# LED_SCH.net
KiCad netlist of a schematic drawn in Altium Designer
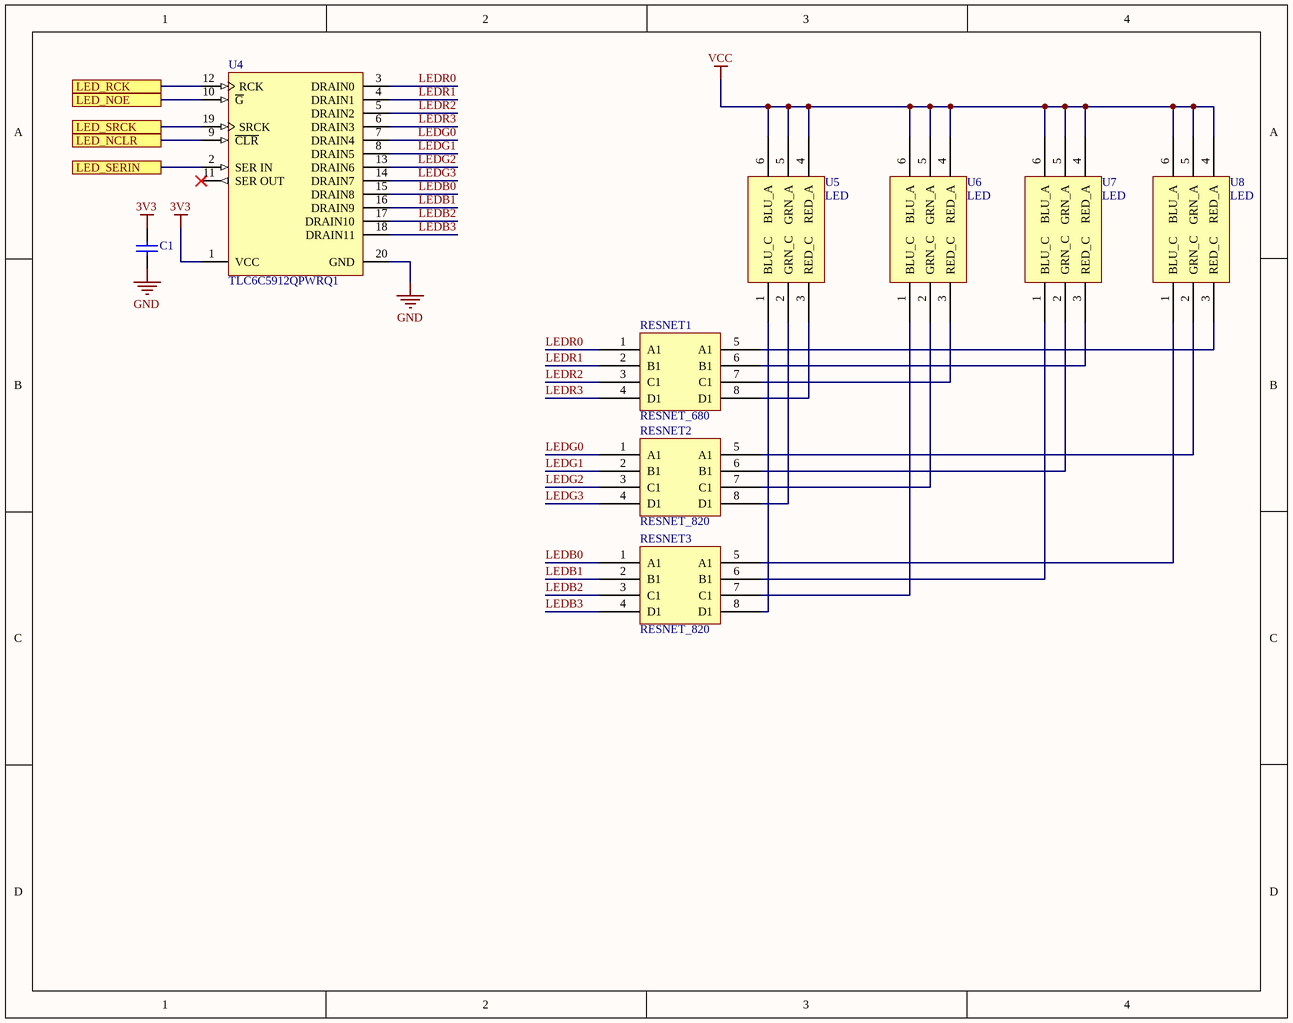
[diagram p0: LED_SCH.SchDoc]

(export (version "E")
  (design (tool "Eeschema 10.0.6"))
  (components
    (comp (ref "C1")
      (value "08055C104KAJ2A")
      (footprint "CAPC2013X140X50NL20T25")
      (fields (field (name "MANUFACTURER") "AVX Interconnect / Elco"))
      (libsource (lib "Altium Content Vault") (part "CAP"))
    )
    (comp (ref "RESNET1")
      (value "RESNET_680")
      (footprint "CAC-80P320X165-8N")
      (description "RES ARRAY 4 RES 680 OHM 2012")
      (libsource (lib "Copter") (part "RESNET_680"))
    )
    (comp (ref "RESNET2")
      (value "RESNET_820")
      (footprint "74X_RESNET")
      (description "RES ARRAY 4 RES 820 OHM 2012")
      (libsource (lib "Copter") (part "RESNET_820"))
    )
    (comp (ref "RESNET3")
      (value "RESNET_820")
      (footprint "74X_RESNET")
      (description "RES ARRAY 4 RES 820 OHM 2012")
      (libsource (lib "Copter") (part "RESNET_820"))
    )
    (comp (ref "U4")
      (value "TLC6C5912QPWRQ1")
      (footprint "PW0020A_N")
      (description "Automotive Power Logic 12-Bit Shift Register LED Driver, PW0020A, LARGE T&R")
      (fields (field (name "PART NUMBER") "TLC6C5912-Q1"))
      (libsource (lib "Altium Content Vault") (part "TI-TLC6C5912-Q1-20_A"))
    )
    (comp (ref "U5") (value "LED") (footprint "PLCC6") (libsource (lib "Copter") (part "LED")))
    (comp (ref "U6") (value "LED") (footprint "PLCC6") (libsource (lib "Copter") (part "LED")))
    (comp (ref "U7") (value "LED") (footprint "PLCC6") (libsource (lib "Copter") (part "LED")))
    (comp (ref "U8") (value "LED") (footprint "PLCC6") (libsource (lib "Copter") (part "LED")))
  )
  (nets
    (net (code "1") (name "/LEDB0") (class "Default")
      (node (ref "RESNET3") (pin "1") (pinfunction "A1_1") (pintype "passive"))
      (node (ref "U4") (pin "15") (pinfunction "DRAIN8_15") (pintype "open_collector"))
    )
    (net (code "2") (name "/LEDB1") (class "Default")
      (node (ref "RESNET3") (pin "2") (pinfunction "B1_2") (pintype "passive"))
      (node (ref "U4") (pin "16") (pinfunction "DRAIN9_16") (pintype "open_collector"))
    )
    (net (code "3") (name "/LEDB2") (class "Default")
      (node (ref "RESNET3") (pin "3") (pinfunction "C1_3") (pintype "passive"))
      (node (ref "U4") (pin "17") (pinfunction "DRAIN10_17") (pintype "open_collector"))
    )
    (net (code "4") (name "/LEDB3") (class "Default")
      (node (ref "RESNET3") (pin "4") (pinfunction "D1_4") (pintype "passive"))
      (node (ref "U4") (pin "18") (pinfunction "DRAIN11_18") (pintype "open_collector"))
    )
    (net (code "5") (name "/LEDG0") (class "Default")
      (node (ref "RESNET2") (pin "1") (pinfunction "A1_1") (pintype "passive"))
      (node (ref "U4") (pin "7") (pinfunction "DRAIN4_7") (pintype "open_collector"))
    )
    (net (code "6") (name "/LEDG1") (class "Default")
      (node (ref "RESNET2") (pin "2") (pinfunction "B1_2") (pintype "passive"))
      (node (ref "U4") (pin "8") (pinfunction "DRAIN5_8") (pintype "open_collector"))
    )
    (net (code "7") (name "/LEDG2") (class "Default")
      (node (ref "RESNET2") (pin "3") (pinfunction "C1_3") (pintype "passive"))
      (node (ref "U4") (pin "13") (pinfunction "DRAIN6_13") (pintype "open_collector"))
    )
    (net (code "8") (name "/LEDG3") (class "Default")
      (node (ref "RESNET2") (pin "4") (pinfunction "D1_4") (pintype "passive"))
      (node (ref "U4") (pin "14") (pinfunction "DRAIN7_14") (pintype "open_collector"))
    )
    (net (code "9") (name "/LEDR0") (class "Default")
      (node (ref "RESNET1") (pin "1") (pinfunction "A1_1") (pintype "passive"))
      (node (ref "U4") (pin "3") (pinfunction "DRAIN0_3") (pintype "open_collector"))
    )
    (net (code "10") (name "/LEDR1") (class "Default")
      (node (ref "RESNET1") (pin "2") (pinfunction "B1_2") (pintype "passive"))
      (node (ref "U4") (pin "4") (pinfunction "DRAIN1_4") (pintype "open_collector"))
    )
    (net (code "11") (name "/LEDR2") (class "Default")
      (node (ref "RESNET1") (pin "3") (pinfunction "C1_3") (pintype "passive"))
      (node (ref "U4") (pin "5") (pinfunction "DRAIN2_5") (pintype "open_collector"))
    )
    (net (code "12") (name "/LEDR3") (class "Default")
      (node (ref "RESNET1") (pin "4") (pinfunction "D1_4") (pintype "passive"))
      (node (ref "U4") (pin "6") (pinfunction "DRAIN3_6") (pintype "open_collector"))
    )
    (net (code "13") (name "/LED_NCLR") (class "Default")
      (node (ref "U4") (pin "9") (pinfunction "~{CLR}_9") (pintype "input"))
    )
    (net (code "14") (name "/LED_NOE") (class "Default")
      (node (ref "U4") (pin "10") (pinfunction "~{G}_10") (pintype "input"))
    )
    (net (code "15") (name "/LED_RCK") (class "Default")
      (node (ref "U4") (pin "12") (pinfunction "RCK_12") (pintype "input"))
    )
    (net (code "16") (name "/LED_SERIN") (class "Default")
      (node (ref "U4") (pin "2") (pinfunction "SER_IN_2") (pintype "input"))
    )
    (net (code "17") (name "/LED_SRCK") (class "Default")
      (node (ref "U4") (pin "19") (pinfunction "SRCK_19") (pintype "input"))
    )
    (net (code "18") (name "3V3") (class "Default")
      (node (ref "C1") (pin "2") (pinfunction "2_2") (pintype "passive"))
      (node (ref "U4") (pin "1") (pinfunction "VCC_1") (pintype "power_in"))
    )
    (net (code "19") (name "GND") (class "Default")
      (node (ref "C1") (pin "1") (pinfunction "1_1") (pintype "passive"))
      (node (ref "U4") (pin "20") (pinfunction "GND_20") (pintype "power_in"))
    )
    (net (code "20") (name "Net-(U5-BLU_C)") (class "Default")
      (node (ref "RESNET3") (pin "8") (pinfunction "D1_8") (pintype "passive"))
      (node (ref "U5") (pin "1") (pinfunction "BLU_C_1") (pintype "passive"))
    )
    (net (code "21") (name "Net-(U5-GRN_C)") (class "Default")
      (node (ref "RESNET2") (pin "8") (pinfunction "D1_8") (pintype "passive"))
      (node (ref "U5") (pin "2") (pinfunction "GRN_C_2") (pintype "passive"))
    )
    (net (code "22") (name "Net-(U5-RED_C)") (class "Default")
      (node (ref "RESNET1") (pin "8") (pinfunction "D1_8") (pintype "passive"))
      (node (ref "U5") (pin "3") (pinfunction "RED_C_3") (pintype "passive"))
    )
    (net (code "23") (name "Net-(U6-BLU_C)") (class "Default")
      (node (ref "RESNET3") (pin "7") (pinfunction "C1_7") (pintype "passive"))
      (node (ref "U6") (pin "1") (pinfunction "BLU_C_1") (pintype "passive"))
    )
    (net (code "24") (name "Net-(U6-GRN_C)") (class "Default")
      (node (ref "RESNET2") (pin "7") (pinfunction "C1_7") (pintype "passive"))
      (node (ref "U6") (pin "2") (pinfunction "GRN_C_2") (pintype "passive"))
    )
    (net (code "25") (name "Net-(U6-RED_C)") (class "Default")
      (node (ref "RESNET1") (pin "7") (pinfunction "C1_7") (pintype "passive"))
      (node (ref "U6") (pin "3") (pinfunction "RED_C_3") (pintype "passive"))
    )
    (net (code "26") (name "Net-(U7-BLU_C)") (class "Default")
      (node (ref "RESNET3") (pin "6") (pinfunction "B1_6") (pintype "passive"))
      (node (ref "U7") (pin "1") (pinfunction "BLU_C_1") (pintype "passive"))
    )
    (net (code "27") (name "Net-(U7-GRN_C)") (class "Default")
      (node (ref "RESNET2") (pin "6") (pinfunction "B1_6") (pintype "passive"))
      (node (ref "U7") (pin "2") (pinfunction "GRN_C_2") (pintype "passive"))
    )
    (net (code "28") (name "Net-(U7-RED_C)") (class "Default")
      (node (ref "RESNET1") (pin "6") (pinfunction "B1_6") (pintype "passive"))
      (node (ref "U7") (pin "3") (pinfunction "RED_C_3") (pintype "passive"))
    )
    (net (code "29") (name "Net-(U8-BLU_C)") (class "Default")
      (node (ref "RESNET3") (pin "5") (pinfunction "A1_5") (pintype "passive"))
      (node (ref "U8") (pin "1") (pinfunction "BLU_C_1") (pintype "passive"))
    )
    (net (code "30") (name "Net-(U8-GRN_C)") (class "Default")
      (node (ref "RESNET2") (pin "5") (pinfunction "A1_5") (pintype "passive"))
      (node (ref "U8") (pin "2") (pinfunction "GRN_C_2") (pintype "passive"))
    )
    (net (code "31") (name "Net-(U8-RED_C)") (class "Default")
      (node (ref "RESNET1") (pin "5") (pinfunction "A1_5") (pintype "passive"))
      (node (ref "U8") (pin "3") (pinfunction "RED_C_3") (pintype "passive"))
    )
    (net (code "32") (name "VCC") (class "Default")
      (node (ref "U5") (pin "4") (pinfunction "RED_A_4") (pintype "passive"))
      (node (ref "U5") (pin "5") (pinfunction "GRN_A_5") (pintype "passive"))
      (node (ref "U5") (pin "6") (pinfunction "BLU_A_6") (pintype "passive"))
      (node (ref "U6") (pin "4") (pinfunction "RED_A_4") (pintype "passive"))
      (node (ref "U6") (pin "5") (pinfunction "GRN_A_5") (pintype "passive"))
      (node (ref "U6") (pin "6") (pinfunction "BLU_A_6") (pintype "passive"))
      (node (ref "U7") (pin "4") (pinfunction "RED_A_4") (pintype "passive"))
      (node (ref "U7") (pin "5") (pinfunction "GRN_A_5") (pintype "passive"))
      (node (ref "U7") (pin "6") (pinfunction "BLU_A_6") (pintype "passive"))
      (node (ref "U8") (pin "4") (pinfunction "RED_A_4") (pintype "passive"))
      (node (ref "U8") (pin "5") (pinfunction "GRN_A_5") (pintype "passive"))
      (node (ref "U8") (pin "6") (pinfunction "BLU_A_6") (pintype "passive"))
    )
    (net (code "33") (name "unconnected-(U4-SER_OUT-Pad11)") (class "Default")
      (node (ref "U4") (pin "11") (pinfunction "SER_OUT_11") (pintype "output+no_connect"))
    )
  )
)
